# MakerTherapyBadge.net
KiCad netlist of a schematic drawn in EAGLE
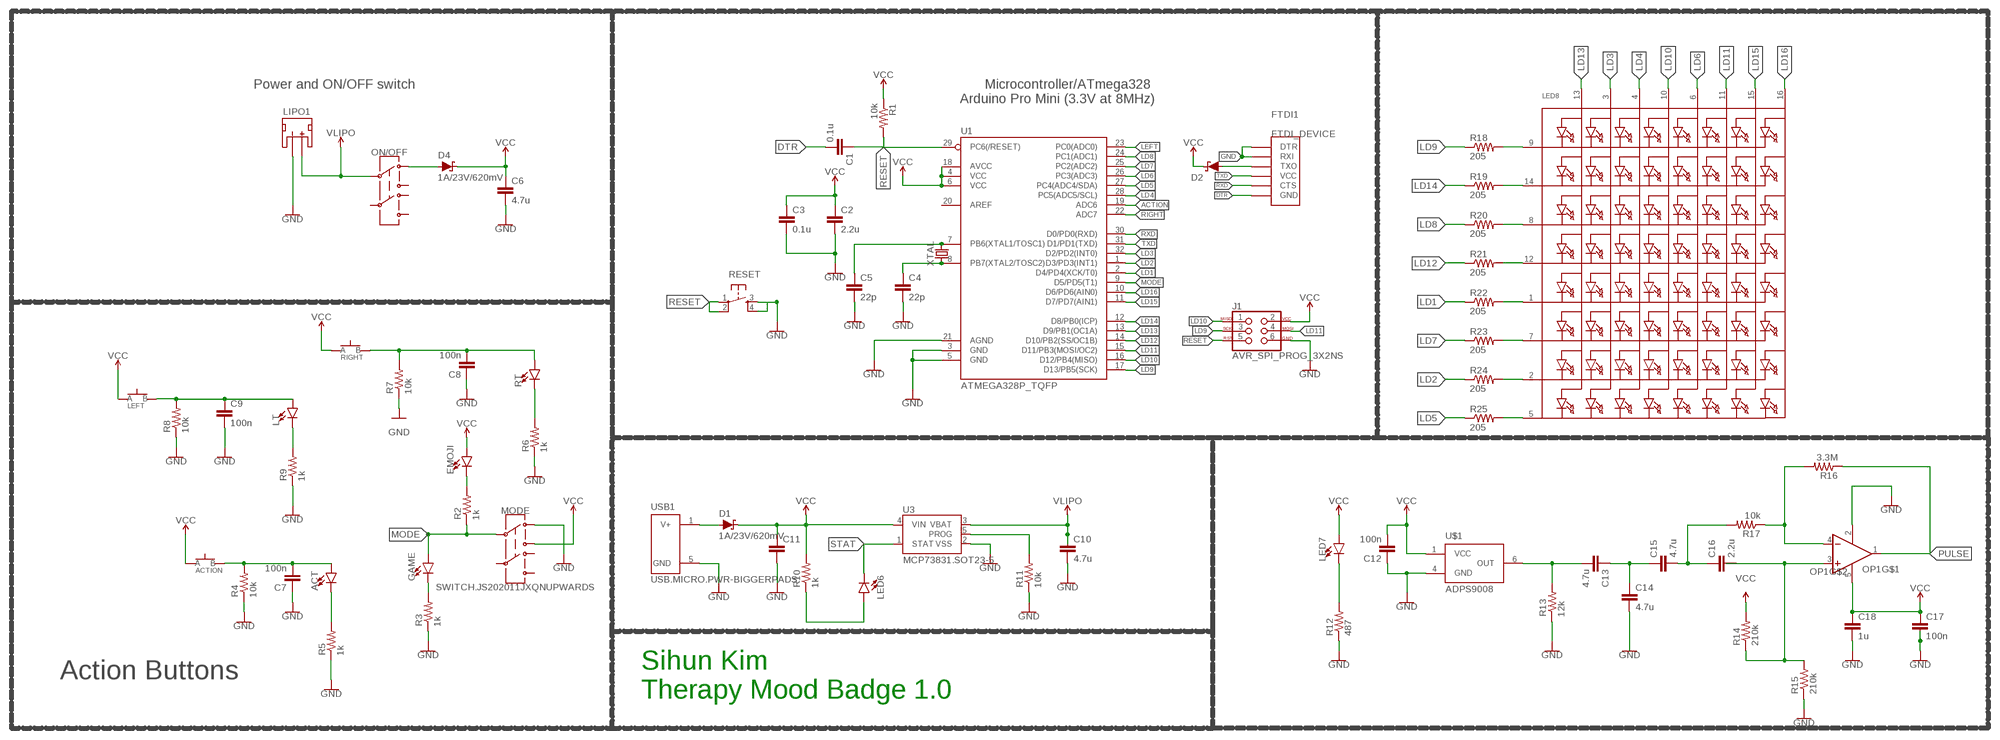
[diagram p0: schematic, sheet 1]

(export (version "E")
  (design (tool "Eeschema 10.0.6"))
  (components
    (comp (ref "ACT")
      (value "LED0603")
      (footprint "eagle-import:LED-0603")
      (libsource (lib "eagle-import") (part "LED0603"))
    )
    (comp (ref "ACTION")
      (value "SPST.KT11P4SM34LFS")
      (footprint "eagle-import:SPST.KT11P4SM34LFS")
      (libsource (lib "eagle-import") (part "SPST.KT11P4SM34LFS"))
    )
    (comp (ref "C1")
      (value "0.1u")
      (footprint "eagle-import:C0603")
      (libsource (lib "eagle-import") (part "CAPACITOR0603"))
    )
    (comp (ref "C2")
      (value "2.2u")
      (footprint "eagle-import:C0603")
      (libsource (lib "eagle-import") (part "CAPACITOR0603"))
    )
    (comp (ref "C3")
      (value "0.1u")
      (footprint "eagle-import:C0603")
      (libsource (lib "eagle-import") (part "CAPACITOR0603"))
    )
    (comp (ref "C4")
      (value "22p")
      (footprint "eagle-import:C0603")
      (libsource (lib "eagle-import") (part "CAPACITOR0603"))
    )
    (comp (ref "C5")
      (value "22p")
      (footprint "eagle-import:C0603")
      (libsource (lib "eagle-import") (part "CAPACITOR0603"))
    )
    (comp (ref "C6")
      (value "4.7u")
      (footprint "eagle-import:C0603")
      (libsource (lib "eagle-import") (part "CAPACITOR0603"))
    )
    (comp (ref "C7")
      (value "100n")
      (footprint "eagle-import:C0603")
      (libsource (lib "eagle-import") (part "CAPACITOR0603"))
    )
    (comp (ref "C8")
      (value "100n")
      (footprint "eagle-import:C0603")
      (libsource (lib "eagle-import") (part "CAPACITOR0603"))
    )
    (comp (ref "C9")
      (value "100n")
      (footprint "eagle-import:C0603")
      (libsource (lib "eagle-import") (part "CAPACITOR0603"))
    )
    (comp (ref "C10")
      (value "4.7u")
      (footprint "eagle-import:C0603")
      (libsource (lib "eagle-import") (part "CAPACITOR0603"))
    )
    (comp (ref "C11")
      (value "CAPACITOR0603")
      (footprint "eagle-import:C0603")
      (libsource (lib "eagle-import") (part "CAPACITOR0603"))
    )
    (comp (ref "C12")
      (value "100n")
      (footprint "eagle-import:C0603")
      (libsource (lib "eagle-import") (part "CAPACITOR0603"))
    )
    (comp (ref "C13")
      (value "4.7u")
      (footprint "eagle-import:C0603")
      (libsource (lib "eagle-import") (part "CAPACITOR0603"))
    )
    (comp (ref "C14")
      (value "4.7u")
      (footprint "eagle-import:C0603")
      (libsource (lib "eagle-import") (part "CAPACITOR0603"))
    )
    (comp (ref "C15")
      (value "4.7u")
      (footprint "eagle-import:C0603")
      (libsource (lib "eagle-import") (part "CAPACITOR0603"))
    )
    (comp (ref "C16")
      (value "2.2u")
      (footprint "eagle-import:C0603")
      (libsource (lib "eagle-import") (part "CAPACITOR0603"))
    )
    (comp (ref "C17")
      (value "100n")
      (footprint "eagle-import:C0603")
      (libsource (lib "eagle-import") (part "CAPACITOR0603"))
    )
    (comp (ref "C18")
      (value "1u")
      (footprint "eagle-import:C0603")
      (libsource (lib "eagle-import") (part "CAPACITOR0603"))
    )
    (comp (ref "D1")
      (value "1A/23V/620mV")
      (footprint "eagle-import:USC")
      (libsource (lib "eagle-import") (part "SCHOTTKY-USC"))
    )
    (comp (ref "D2")
      (value "SCHOTTKY-USC")
      (footprint "eagle-import:USC")
      (libsource (lib "eagle-import") (part "SCHOTTKY-USC"))
    )
    (comp (ref "D4")
      (value "1A/23V/620mV")
      (footprint "eagle-import:USC")
      (libsource (lib "eagle-import") (part "SCHOTTKY-USC"))
    )
    (comp (ref "EMOJI")
      (value "LED0603")
      (footprint "eagle-import:LED-0603")
      (libsource (lib "eagle-import") (part "LED0603"))
    )
    (comp (ref "FTDI1")
      (value "FTDI_DEVICE")
      (footprint "eagle-import:FTDI_DEVICE")
      (libsource (lib "eagle-import") (part "FTDI_DEVICE"))
    )
    (comp (ref "GAME")
      (value "LED0603")
      (footprint "eagle-import:LED-0603")
      (libsource (lib "eagle-import") (part "LED0603"))
    )
    (comp (ref "J1")
      (value "AVR_SPI_PROG_3X2NS")
      (footprint "eagle-import:2X3-NS")
      (libsource (lib "eagle-import") (part "AVR_SPI_PROG_3X2NS"))
    )
    (comp (ref "LED6")
      (value "LED0603")
      (footprint "eagle-import:LED-0603")
      (libsource (lib "eagle-import") (part "LED0603"))
    )
    (comp (ref "LED7")
      (value "LED0603")
      (footprint "eagle-import:LED-0603")
      (libsource (lib "eagle-import") (part "LED0603"))
    )
    (comp (ref "LED8")
      (value "SEGMENT_8X8_ROWCATHODEM12A881UR")
      (footprint "eagle-import:SEGMENT_BL-M12A881UR")
      (libsource (lib "eagle-import") (part "SEGMENT_8X8_ROWCATHODEM12A881UR"))
    )
    (comp (ref "LEFT")
      (value "SPST.KT11P4SM34LFS")
      (footprint "eagle-import:SPST.KT11P4SM34LFS")
      (libsource (lib "eagle-import") (part "SPST.KT11P4SM34LFS"))
    )
    (comp (ref "LIPO1")
      (value "JST_2MM_MALE")
      (footprint "eagle-import:JST-2-SMD")
      (libsource (lib "eagle-import") (part "JST_2MM_MALE"))
    )
    (comp (ref "LT")
      (value "LED0603")
      (footprint "eagle-import:LED-0603")
      (libsource (lib "eagle-import") (part "LED0603"))
    )
    (comp (ref "MODE")
      (value "SWITCH.JS202011JXQNUPWARDS")
      (footprint "eagle-import:SWITCH.00")
      (libsource (lib "eagle-import") (part "SWITCH.JS202011JXQNUPWARDS"))
    )
    (comp (ref "ON/OFF")
      (value "SWITCH.JS202011JXQNUPWARDS")
      (footprint "eagle-import:SWITCH.00")
      (libsource (lib "eagle-import") (part "SWITCH.JS202011JXQNUPWARDS"))
    )
    (comp (ref "OP1")
      (value "OP-SINGLEOT")
      (footprint "eagle-import:SOT23-5")
      (libsource (lib "eagle-import") (part "OP-SINGLEOT"))
    )
    (comp (ref "R1")
      (value "10k")
      (footprint "eagle-import:R0603")
      (libsource (lib "eagle-import") (part "RESISTOR0603"))
    )
    (comp (ref "R2")
      (value "1k")
      (footprint "eagle-import:R0603")
      (libsource (lib "eagle-import") (part "RESISTOR0603"))
    )
    (comp (ref "R3")
      (value "1k")
      (footprint "eagle-import:R0603")
      (libsource (lib "eagle-import") (part "RESISTOR0603"))
    )
    (comp (ref "R4")
      (value "10k")
      (footprint "eagle-import:R0603")
      (libsource (lib "eagle-import") (part "RESISTOR0603"))
    )
    (comp (ref "R5")
      (value "1k")
      (footprint "eagle-import:R0603")
      (libsource (lib "eagle-import") (part "RESISTOR0603"))
    )
    (comp (ref "R6")
      (value "1k")
      (footprint "eagle-import:R0603")
      (libsource (lib "eagle-import") (part "RESISTOR0603"))
    )
    (comp (ref "R7")
      (value "10k")
      (footprint "eagle-import:R0603")
      (libsource (lib "eagle-import") (part "RESISTOR0603"))
    )
    (comp (ref "R8")
      (value "10k")
      (footprint "eagle-import:R0603")
      (libsource (lib "eagle-import") (part "RESISTOR0603"))
    )
    (comp (ref "R9")
      (value "1k")
      (footprint "eagle-import:R0603")
      (libsource (lib "eagle-import") (part "RESISTOR0603"))
    )
    (comp (ref "R10")
      (value "1k")
      (footprint "eagle-import:R0603")
      (libsource (lib "eagle-import") (part "RESISTOR0603"))
    )
    (comp (ref "R11")
      (value "10k")
      (footprint "eagle-import:R0603")
      (libsource (lib "eagle-import") (part "RESISTOR0603"))
    )
    (comp (ref "R12")
      (value "487")
      (footprint "eagle-import:R0603")
      (libsource (lib "eagle-import") (part "RESISTOR0603"))
    )
    (comp (ref "R13")
      (value "12k")
      (footprint "eagle-import:R0603")
      (libsource (lib "eagle-import") (part "RESISTOR0603"))
    )
    (comp (ref "R14")
      (value "210k")
      (footprint "eagle-import:R0603")
      (libsource (lib "eagle-import") (part "RESISTOR0603"))
    )
    (comp (ref "R15")
      (value "210k")
      (footprint "eagle-import:R0603")
      (libsource (lib "eagle-import") (part "RESISTOR0603"))
    )
    (comp (ref "R16")
      (value "3.3M")
      (footprint "eagle-import:R0603")
      (libsource (lib "eagle-import") (part "RESISTOR0603"))
    )
    (comp (ref "R17")
      (value "10k")
      (footprint "eagle-import:R0603")
      (libsource (lib "eagle-import") (part "RESISTOR0603"))
    )
    (comp (ref "R18")
      (value "205")
      (footprint "eagle-import:R0603")
      (libsource (lib "eagle-import") (part "RESISTOR0603"))
    )
    (comp (ref "R19")
      (value "205")
      (footprint "eagle-import:R0603")
      (libsource (lib "eagle-import") (part "RESISTOR0603"))
    )
    (comp (ref "R20")
      (value "205")
      (footprint "eagle-import:R0603")
      (libsource (lib "eagle-import") (part "RESISTOR0603"))
    )
    (comp (ref "R21")
      (value "205")
      (footprint "eagle-import:R0603")
      (libsource (lib "eagle-import") (part "RESISTOR0603"))
    )
    (comp (ref "R22")
      (value "205")
      (footprint "eagle-import:R0603")
      (libsource (lib "eagle-import") (part "RESISTOR0603"))
    )
    (comp (ref "R23")
      (value "205")
      (footprint "eagle-import:R0603")
      (libsource (lib "eagle-import") (part "RESISTOR0603"))
    )
    (comp (ref "R24")
      (value "205")
      (footprint "eagle-import:R0603")
      (libsource (lib "eagle-import") (part "RESISTOR0603"))
    )
    (comp (ref "R25")
      (value "205")
      (footprint "eagle-import:R0603")
      (libsource (lib "eagle-import") (part "RESISTOR0603"))
    )
    (comp (ref "RESET")
      (value "SPST-PTS830GG140")
      (footprint "eagle-import:BUTTON-GULLWING")
      (libsource (lib "eagle-import") (part "SPST-PTS830GG140"))
    )
    (comp (ref "RIGHT")
      (value "SPST.KT11P4SM34LFS")
      (footprint "eagle-import:SPST.KT11P4SM34LFS")
      (libsource (lib "eagle-import") (part "SPST.KT11P4SM34LFS"))
    )
    (comp (ref "RT")
      (value "LED0603")
      (footprint "eagle-import:LED-0603")
      (libsource (lib "eagle-import") (part "LED0603"))
    )
    (comp (ref "U$1")
      (value "ADPS9008")
      (footprint "eagle-import:6-PIN.CHIPLED")
      (libsource (lib "eagle-import") (part "ADPS9008"))
    )
    (comp (ref "U1")
      (value "ATMEGA328P_TQFP")
      (footprint "eagle-import:TQFP32-08")
      (libsource (lib "eagle-import") (part "ATMEGA328P_TQFP"))
    )
    (comp (ref "U3")
      (value "MCP73831.SOT23-5")
      (footprint "eagle-import:SOT23-5")
      (libsource (lib "eagle-import") (part "MCP73831.SOT23-5"))
    )
    (comp (ref "USB1")
      (value "USB.MICRO.PWR-BIGGERPADS")
      (footprint "eagle-import:USB-MICRO-01.BIGGERPADS.PWR")
      (libsource (lib "eagle-import") (part "USB.MICRO.PWR-BIGGERPADS"))
    )
    (comp (ref "XTAL")
      (value "CRYSTAL-CA-310")
      (footprint "eagle-import:CA-301")
      (libsource (lib "eagle-import") (part "CRYSTAL-CA-310"))
    )
  )
  (nets
    (net (code "1") (name "ACTION") (class "Default")
      (node (ref "U1") (pin "19") (pinfunction "ADC6_19") (pintype "bidirectional"))
    )
    (net (code "2") (name "DTR") (class "Default")
      (node (ref "C1") (pin "2") (pinfunction "2_2") (pintype "passive"))
      (node (ref "FTDI1") (pin "GND") (pinfunction "GND_GND") (pintype "bidirectional"))
    )
    (net (code "3") (name "GND") (class "Default")
      (node (ref "C10") (pin "2") (pinfunction "2_2") (pintype "passive"))
      (node (ref "C11") (pin "2") (pinfunction "2_2") (pintype "passive"))
      (node (ref "C12") (pin "1") (pinfunction "1_1") (pintype "passive"))
      (node (ref "C14") (pin "2") (pinfunction "2_2") (pintype "passive"))
      (node (ref "C17") (pin "2") (pinfunction "2_2") (pintype "passive"))
      (node (ref "C18") (pin "2") (pinfunction "2_2") (pintype "passive"))
      (node (ref "C2") (pin "2") (pinfunction "2_2") (pintype "passive"))
      (node (ref "C3") (pin "2") (pinfunction "2_2") (pintype "passive"))
      (node (ref "C4") (pin "2") (pinfunction "2_2") (pintype "passive"))
      (node (ref "C5") (pin "2") (pinfunction "2_2") (pintype "passive"))
      (node (ref "C6") (pin "2") (pinfunction "2_2") (pintype "passive"))
      (node (ref "C7") (pin "1") (pinfunction "1_1") (pintype "passive"))
      (node (ref "C8") (pin "1") (pinfunction "1_1") (pintype "passive"))
      (node (ref "C9") (pin "2") (pinfunction "2_2") (pintype "passive"))
      (node (ref "FTDI1") (pin "DTR") (pinfunction "DTR_DTR") (pintype "bidirectional"))
      (node (ref "FTDI1") (pin "TXO") (pinfunction "RXI_TXO") (pintype "bidirectional"))
      (node (ref "J1") (pin "6") (pinfunction "6_6") (pintype "passive"))
      (node (ref "LIPO1") (pin "1") (pinfunction "-_1") (pintype "bidirectional"))
      (node (ref "MODE") (pin "1") (pinfunction "1_1") (pintype "bidirectional"))
      (node (ref "OP1") (pin "2") (pinfunction "V-_2") (pintype "power_in"))
      (node (ref "R11") (pin "1") (pinfunction "1_1") (pintype "passive"))
      (node (ref "R12") (pin "1") (pinfunction "1_1") (pintype "passive"))
      (node (ref "R13") (pin "1") (pinfunction "1_1") (pintype "passive"))
      (node (ref "R15") (pin "1") (pinfunction "1_1") (pintype "passive"))
      (node (ref "R3") (pin "1") (pinfunction "1_1") (pintype "passive"))
      (node (ref "R4") (pin "1") (pinfunction "1_1") (pintype "passive"))
      (node (ref "R5") (pin "1") (pinfunction "1_1") (pintype "passive"))
      (node (ref "R6") (pin "1") (pinfunction "1_1") (pintype "passive"))
      (node (ref "R7") (pin "1") (pinfunction "1_1") (pintype "passive"))
      (node (ref "R8") (pin "1") (pinfunction "1_1") (pintype "passive"))
      (node (ref "R9") (pin "1") (pinfunction "1_1") (pintype "passive"))
      (node (ref "RESET") (pin "3") (pinfunction "3_3") (pintype "passive"))
      (node (ref "RESET") (pin "4") (pinfunction "4_4") (pintype "passive"))
      (node (ref "U$1") (pin "4") (pinfunction "GND_4") (pintype "bidirectional"))
      (node (ref "U1") (pin "21") (pinfunction "AGND_21") (pintype "bidirectional"))
      (node (ref "U1") (pin "3") (pinfunction "GND_3") (pintype "bidirectional"))
      (node (ref "U1") (pin "5") (pinfunction "GND_5") (pintype "bidirectional"))
      (node (ref "U3") (pin "2") (pinfunction "VSS_2") (pintype "power_in"))
      (node (ref "USB1") (pin "5") (pinfunction "GND_5") (pintype "bidirectional"))
    )
    (net (code "4") (name "LD1") (class "Default")
      (node (ref "R22") (pin "1") (pinfunction "1_1") (pintype "passive"))
      (node (ref "U1") (pin "2") (pinfunction "D4/PD4(XCK/T0)_2") (pintype "bidirectional"))
    )
    (net (code "5") (name "LD2") (class "Default")
      (node (ref "R24") (pin "1") (pinfunction "1_1") (pintype "passive"))
      (node (ref "U1") (pin "1") (pinfunction "D3/PD3(INT1)_1") (pintype "bidirectional"))
    )
    (net (code "6") (name "LD3") (class "Default")
      (node (ref "LED8") (pin "3") (pinfunction "A2_3") (pintype "bidirectional"))
      (node (ref "U1") (pin "32") (pinfunction "D2/PD2(INT0)_32") (pintype "bidirectional"))
    )
    (net (code "7") (name "LD4") (class "Default")
      (node (ref "LED8") (pin "4") (pinfunction "A3_4") (pintype "bidirectional"))
      (node (ref "U1") (pin "28") (pinfunction "PC5(ADC5/SCL)_28") (pintype "bidirectional"))
    )
    (net (code "8") (name "LD5") (class "Default")
      (node (ref "R25") (pin "1") (pinfunction "1_1") (pintype "passive"))
      (node (ref "U1") (pin "27") (pinfunction "PC4(ADC4/SDA)_27") (pintype "bidirectional"))
    )
    (net (code "9") (name "LD6") (class "Default")
      (node (ref "LED8") (pin "6") (pinfunction "A5_6") (pintype "bidirectional"))
      (node (ref "U1") (pin "26") (pinfunction "PC3(ADC3)_26") (pintype "bidirectional"))
    )
    (net (code "10") (name "LD7") (class "Default")
      (node (ref "R23") (pin "1") (pinfunction "1_1") (pintype "passive"))
      (node (ref "U1") (pin "25") (pinfunction "PC2(ADC2)_25") (pintype "bidirectional"))
    )
    (net (code "11") (name "LD8") (class "Default")
      (node (ref "R20") (pin "1") (pinfunction "1_1") (pintype "passive"))
      (node (ref "U1") (pin "24") (pinfunction "PC1(ADC1)_24") (pintype "bidirectional"))
    )
    (net (code "12") (name "LD9") (class "Default")
      (node (ref "J1") (pin "3") (pinfunction "3_3") (pintype "passive"))
      (node (ref "R18") (pin "1") (pinfunction "1_1") (pintype "passive"))
      (node (ref "U1") (pin "17") (pinfunction "D13/PB5(SCK)_17") (pintype "bidirectional"))
    )
    (net (code "13") (name "LD10") (class "Default")
      (node (ref "J1") (pin "1") (pinfunction "1_1") (pintype "passive"))
      (node (ref "LED8") (pin "10") (pinfunction "A4_10") (pintype "bidirectional"))
      (node (ref "U1") (pin "16") (pinfunction "D12/PB4(MISO)_16") (pintype "bidirectional"))
    )
    (net (code "14") (name "LD11") (class "Default")
      (node (ref "J1") (pin "4") (pinfunction "4_4") (pintype "passive"))
      (node (ref "LED8") (pin "11") (pinfunction "A6_11") (pintype "bidirectional"))
      (node (ref "U1") (pin "15") (pinfunction "D11/PB3(MOSI/OC2)_15") (pintype "bidirectional"))
    )
    (net (code "15") (name "LD12") (class "Default")
      (node (ref "R21") (pin "1") (pinfunction "1_1") (pintype "passive"))
      (node (ref "U1") (pin "14") (pinfunction "D10/PB2(SS/OC1B)_14") (pintype "bidirectional"))
    )
    (net (code "16") (name "LD13") (class "Default")
      (node (ref "LED8") (pin "13") (pinfunction "A1_13") (pintype "bidirectional"))
      (node (ref "U1") (pin "13") (pinfunction "D9/PB1(OC1A)_13") (pintype "bidirectional"))
    )
    (net (code "17") (name "LD14") (class "Default")
      (node (ref "R19") (pin "1") (pinfunction "1_1") (pintype "passive"))
      (node (ref "U1") (pin "12") (pinfunction "D8/PB0(ICP)_12") (pintype "bidirectional"))
    )
    (net (code "18") (name "LD15") (class "Default")
      (node (ref "LED8") (pin "15") (pinfunction "A7_15") (pintype "bidirectional"))
      (node (ref "U1") (pin "11") (pinfunction "D7/PD7(AIN1)_11") (pintype "bidirectional"))
    )
    (net (code "19") (name "LD16") (class "Default")
      (node (ref "LED8") (pin "16") (pinfunction "A8_16") (pintype "bidirectional"))
      (node (ref "U1") (pin "10") (pinfunction "D6/PD6(AIN0)_10") (pintype "bidirectional"))
    )
    (net (code "20") (name "LEFT") (class "Default")
      (node (ref "U1") (pin "23") (pinfunction "PC0(ADC0)_23") (pintype "bidirectional"))
    )
    (net (code "21") (name "MODE") (class "Default")
      (node (ref "GAME") (pin "A") (pinfunction "A_A") (pintype "passive"))
      (node (ref "MODE") (pin "2") (pinfunction "2_2") (pintype "bidirectional"))
      (node (ref "R2") (pin "1") (pinfunction "1_1") (pintype "passive"))
      (node (ref "U1") (pin "9") (pinfunction "D5/PD5(T1)_9") (pintype "bidirectional"))
    )
    (net (code "22") (name "Net-(ACT-PadA)") (class "Default")
      (node (ref "ACT") (pin "A") (pinfunction "A_A") (pintype "passive"))
      (node (ref "ACTION") (pin "3") (pinfunction "B_3") (pintype "bidirectional"))
      (node (ref "ACTION") (pin "4") (pinfunction "B_4") (pintype "bidirectional"))
      (node (ref "C7") (pin "2") (pinfunction "2_2") (pintype "passive"))
      (node (ref "R4") (pin "2") (pinfunction "2_2") (pintype "passive"))
    )
    (net (code "23") (name "Net-(ACT-PadC)") (class "Default")
      (node (ref "ACT") (pin "C") (pinfunction "C_C") (pintype "passive"))
      (node (ref "R5") (pin "2") (pinfunction "2_2") (pintype "passive"))
    )
    (net (code "24") (name "Net-(C8-Pad2)") (class "Default")
      (node (ref "C8") (pin "2") (pinfunction "2_2") (pintype "passive"))
      (node (ref "R7") (pin "2") (pinfunction "2_2") (pintype "passive"))
      (node (ref "RIGHT") (pin "3") (pinfunction "B_3") (pintype "bidirectional"))
      (node (ref "RIGHT") (pin "4") (pinfunction "B_4") (pintype "bidirectional"))
      (node (ref "RT") (pin "A") (pinfunction "A_A") (pintype "passive"))
    )
    (net (code "25") (name "Net-(C9-Pad1)") (class "Default")
      (node (ref "C9") (pin "1") (pinfunction "1_1") (pintype "passive"))
      (node (ref "LEFT") (pin "3") (pinfunction "B_3") (pintype "bidirectional"))
      (node (ref "LEFT") (pin "4") (pinfunction "B_4") (pintype "bidirectional"))
      (node (ref "LT") (pin "A") (pinfunction "A_A") (pintype "passive"))
      (node (ref "R8") (pin "2") (pinfunction "2_2") (pintype "passive"))
    )
    (net (code "26") (name "Net-(C13-Pad1)") (class "Default")
      (node (ref "C13") (pin "1") (pinfunction "1_1") (pintype "passive"))
      (node (ref "C14") (pin "1") (pinfunction "1_1") (pintype "passive"))
      (node (ref "C15") (pin "1") (pinfunction "1_1") (pintype "passive"))
    )
    (net (code "27") (name "Net-(C15-Pad2)") (class "Default")
      (node (ref "C15") (pin "2") (pinfunction "2_2") (pintype "passive"))
      (node (ref "C16") (pin "1") (pinfunction "1_1") (pintype "passive"))
      (node (ref "R17") (pin "2") (pinfunction "2_2") (pintype "passive"))
    )
    (net (code "28") (name "Net-(D1-A)") (class "Default")
      (node (ref "D1") (pin "+") (pinfunction "A_+") (pintype "passive"))
      (node (ref "USB1") (pin "1") (pinfunction "V+_1") (pintype "bidirectional"))
    )
    (net (code "29") (name "Net-(D2-A)") (class "Default")
      (node (ref "D2") (pin "+") (pinfunction "A_+") (pintype "passive"))
      (node (ref "FTDI1") (pin "RXI") (pinfunction "TXO_RXI") (pintype "bidirectional"))
    )
    (net (code "30") (name "Net-(D4-A)") (class "Default")
      (node (ref "D4") (pin "+") (pinfunction "A_+") (pintype "passive"))
      (node (ref "ON/OFF") (pin "1") (pinfunction "1_1") (pintype "bidirectional"))
    )
    (net (code "31") (name "Net-(EMOJI-PadC)") (class "Default")
      (node (ref "EMOJI") (pin "C") (pinfunction "C_C") (pintype "passive"))
      (node (ref "R2") (pin "2") (pinfunction "2_2") (pintype "passive"))
    )
    (net (code "32") (name "Net-(GAME-PadC)") (class "Default")
      (node (ref "GAME") (pin "C") (pinfunction "C_C") (pintype "passive"))
      (node (ref "R3") (pin "2") (pinfunction "2_2") (pintype "passive"))
    )
    (net (code "33") (name "Net-(LED6-PadA)") (class "Default")
      (node (ref "LED6") (pin "A") (pinfunction "A_A") (pintype "passive"))
      (node (ref "R10") (pin "1") (pinfunction "1_1") (pintype "passive"))
    )
    (net (code "34") (name "Net-(LED7-PadC)") (class "Default")
      (node (ref "LED7") (pin "C") (pinfunction "C_C") (pintype "passive"))
      (node (ref "R12") (pin "2") (pinfunction "2_2") (pintype "passive"))
    )
    (net (code "35") (name "Net-(LED8-K1)") (class "Default")
      (node (ref "LED8") (pin "9") (pinfunction "K1_9") (pintype "bidirectional"))
      (node (ref "R18") (pin "2") (pinfunction "2_2") (pintype "passive"))
    )
    (net (code "36") (name "Net-(LED8-K2)") (class "Default")
      (node (ref "LED8") (pin "14") (pinfunction "K2_14") (pintype "bidirectional"))
      (node (ref "R19") (pin "2") (pinfunction "2_2") (pintype "passive"))
    )
    (net (code "37") (name "Net-(LED8-K3)") (class "Default")
      (node (ref "LED8") (pin "8") (pinfunction "K3_8") (pintype "bidirectional"))
      (node (ref "R20") (pin "2") (pinfunction "2_2") (pintype "passive"))
    )
    (net (code "38") (name "Net-(LED8-K4)") (class "Default")
      (node (ref "LED8") (pin "12") (pinfunction "K4_12") (pintype "bidirectional"))
      (node (ref "R21") (pin "2") (pinfunction "2_2") (pintype "passive"))
    )
    (net (code "39") (name "Net-(LED8-K5)") (class "Default")
      (node (ref "LED8") (pin "1") (pinfunction "K5_1") (pintype "bidirectional"))
      (node (ref "R22") (pin "2") (pinfunction "2_2") (pintype "passive"))
    )
    (net (code "40") (name "Net-(LED8-K6)") (class "Default")
      (node (ref "LED8") (pin "7") (pinfunction "K6_7") (pintype "bidirectional"))
      (node (ref "R23") (pin "2") (pinfunction "2_2") (pintype "passive"))
    )
    (net (code "41") (name "Net-(LED8-K7)") (class "Default")
      (node (ref "LED8") (pin "2") (pinfunction "K7_2") (pintype "bidirectional"))
      (node (ref "R24") (pin "2") (pinfunction "2_2") (pintype "passive"))
    )
    (net (code "42") (name "Net-(LED8-K8)") (class "Default")
      (node (ref "LED8") (pin "5") (pinfunction "K8_5") (pintype "bidirectional"))
      (node (ref "R25") (pin "2") (pinfunction "2_2") (pintype "passive"))
    )
    (net (code "43") (name "Net-(LT-PadC)") (class "Default")
      (node (ref "LT") (pin "C") (pinfunction "C_C") (pintype "passive"))
      (node (ref "R9") (pin "2") (pinfunction "2_2") (pintype "passive"))
    )
    (net (code "44") (name "Net-(OP1A-+IN)") (class "Default")
      (node (ref "C16") (pin "2") (pinfunction "2_2") (pintype "passive"))
      (node (ref "OP1") (pin "3") (pinfunction "+IN_3") (pintype "input"))
      (node (ref "R14") (pin "1") (pinfunction "1_1") (pintype "passive"))
      (node (ref "R15") (pin "2") (pinfunction "2_2") (pintype "passive"))
    )
    (net (code "45") (name "Net-(OP1A--IN)") (class "Default")
      (node (ref "OP1") (pin "4") (pinfunction "-IN_4") (pintype "input"))
      (node (ref "R16") (pin "2") (pinfunction "2_2") (pintype "passive"))
      (node (ref "R17") (pin "1") (pinfunction "1_1") (pintype "passive"))
    )
    (net (code "46") (name "Net-(R6-Pad2)") (class "Default")
      (node (ref "R6") (pin "2") (pinfunction "2_2") (pintype "passive"))
      (node (ref "RT") (pin "C") (pinfunction "C_C") (pintype "passive"))
    )
    (net (code "47") (name "Net-(U$1-OUT)") (class "Default")
      (node (ref "C13") (pin "2") (pinfunction "2_2") (pintype "passive"))
      (node (ref "R13") (pin "2") (pinfunction "2_2") (pintype "passive"))
      (node (ref "U$1") (pin "6") (pinfunction "OUT_6") (pintype "bidirectional"))
    )
    (net (code "48") (name "Net-(U1-PB6(XTAL1{slash}TOSC1))") (class "Default")
      (node (ref "C5") (pin "1") (pinfunction "1_1") (pintype "passive"))
      (node (ref "U1") (pin "7") (pinfunction "PB6(XTAL1/TOSC1)_7") (pintype "bidirectional"))
      (node (ref "XTAL") (pin "2") (pinfunction "2_2") (pintype "passive"))
    )
    (net (code "49") (name "Net-(U1-PB7(XTAL2{slash}TOSC2))") (class "Default")
      (node (ref "C4") (pin "1") (pinfunction "1_1") (pintype "passive"))
      (node (ref "U1") (pin "8") (pinfunction "PB7(XTAL2/TOSC2)_8") (pintype "bidirectional"))
      (node (ref "XTAL") (pin "1") (pinfunction "1_1") (pintype "passive"))
    )
    (net (code "50") (name "Net-(U3-PROG)") (class "Default")
      (node (ref "R11") (pin "2") (pinfunction "2_2") (pintype "passive"))
      (node (ref "U3") (pin "5") (pinfunction "PROG_5") (pintype "input"))
    )
    (net (code "51") (name "PULSE") (class "Default")
      (node (ref "OP1") (pin "1") (pinfunction "OUT_1") (pintype "output"))
      (node (ref "R16") (pin "1") (pinfunction "1_1") (pintype "passive"))
    )
    (net (code "52") (name "RESET") (class "Default")
      (node (ref "C1") (pin "1") (pinfunction "1_1") (pintype "passive"))
      (node (ref "J1") (pin "5") (pinfunction "5_5") (pintype "passive"))
      (node (ref "R1") (pin "2") (pinfunction "2_2") (pintype "passive"))
      (node (ref "RESET") (pin "1") (pinfunction "1_1") (pintype "passive"))
      (node (ref "RESET") (pin "2") (pinfunction "2_2") (pintype "passive"))
      (node (ref "U1") (pin "29") (pinfunction "PC6(/RESET)_29") (pintype "bidirectional"))
    )
    (net (code "53") (name "RIGHT") (class "Default")
      (node (ref "U1") (pin "22") (pinfunction "ADC7_22") (pintype "bidirectional"))
    )
    (net (code "54") (name "RXD") (class "Default")
      (node (ref "FTDI1") (pin "CTS") (pinfunction "CTS_CTS") (pintype "bidirectional"))
      (node (ref "U1") (pin "30") (pinfunction "D0/PD0(RXD)_30") (pintype "bidirectional"))
    )
    (net (code "55") (name "STAT") (class "Default")
      (node (ref "LED6") (pin "C") (pinfunction "C_C") (pintype "passive"))
      (node (ref "U3") (pin "1") (pinfunction "STAT_1") (pintype "output"))
    )
    (net (code "56") (name "TXD") (class "Default")
      (node (ref "FTDI1") (pin "VCC") (pinfunction "VCC_VCC") (pintype "bidirectional"))
      (node (ref "U1") (pin "31") (pinfunction "D1/PD1(TXD)_31") (pintype "bidirectional"))
    )
    (net (code "57") (name "VCC") (class "Default")
      (node (ref "ACTION") (pin "1") (pinfunction "A_1") (pintype "bidirectional"))
      (node (ref "ACTION") (pin "2") (pinfunction "A_2") (pintype "bidirectional"))
      (node (ref "C11") (pin "1") (pinfunction "1_1") (pintype "passive"))
      (node (ref "C12") (pin "2") (pinfunction "2_2") (pintype "passive"))
      (node (ref "C17") (pin "1") (pinfunction "1_1") (pintype "passive"))
      (node (ref "C18") (pin "1") (pinfunction "1_1") (pintype "passive"))
      (node (ref "C2") (pin "1") (pinfunction "1_1") (pintype "passive"))
      (node (ref "C3") (pin "1") (pinfunction "1_1") (pintype "passive"))
      (node (ref "C6") (pin "1") (pinfunction "1_1") (pintype "passive"))
      (node (ref "D1") (pin "-") (pinfunction "C_-") (pintype "passive"))
      (node (ref "D2") (pin "-") (pinfunction "C_-") (pintype "passive"))
      (node (ref "D4") (pin "-") (pinfunction "C_-") (pintype "passive"))
      (node (ref "EMOJI") (pin "A") (pinfunction "A_A") (pintype "passive"))
      (node (ref "J1") (pin "2") (pinfunction "2_2") (pintype "passive"))
      (node (ref "LED7") (pin "A") (pinfunction "A_A") (pintype "passive"))
      (node (ref "LEFT") (pin "1") (pinfunction "A_1") (pintype "bidirectional"))
      (node (ref "LEFT") (pin "2") (pinfunction "A_2") (pintype "bidirectional"))
      (node (ref "MODE") (pin "3") (pinfunction "3_3") (pintype "bidirectional"))
      (node (ref "OP1") (pin "5") (pinfunction "V+_5") (pintype "power_in"))
      (node (ref "R1") (pin "1") (pinfunction "1_1") (pintype "passive"))
      (node (ref "R10") (pin "2") (pinfunction "2_2") (pintype "passive"))
      (node (ref "R14") (pin "2") (pinfunction "2_2") (pintype "passive"))
      (node (ref "RIGHT") (pin "1") (pinfunction "A_1") (pintype "bidirectional"))
      (node (ref "RIGHT") (pin "2") (pinfunction "A_2") (pintype "bidirectional"))
      (node (ref "U$1") (pin "1") (pinfunction "VCC_1") (pintype "bidirectional"))
      (node (ref "U1") (pin "18") (pinfunction "AVCC_18") (pintype "bidirectional"))
      (node (ref "U1") (pin "4") (pinfunction "VCC_4") (pintype "bidirectional"))
      (node (ref "U1") (pin "6") (pinfunction "VCC_6") (pintype "bidirectional"))
      (node (ref "U3") (pin "4") (pinfunction "VIN_4") (pintype "power_in"))
    )
    (net (code "58") (name "VLIPO") (class "Default")
      (node (ref "C10") (pin "1") (pinfunction "1_1") (pintype "passive"))
      (node (ref "LIPO1") (pin "2") (pinfunction "+_2") (pintype "bidirectional"))
      (node (ref "ON/OFF") (pin "2") (pinfunction "2_2") (pintype "bidirectional"))
      (node (ref "U3") (pin "3") (pinfunction "VBAT_3") (pintype "power_in"))
    )
    (net (code "59") (name "unconnected-(LIPO1-PAD1-PadNC1)") (class "Default")
      (node (ref "LIPO1") (pin "NC1") (pinfunction "PAD1_NC1") (pintype "bidirectional"))
    )
    (net (code "60") (name "unconnected-(LIPO1-PAD2-PadNC2)") (class "Default")
      (node (ref "LIPO1") (pin "NC2") (pinfunction "PAD2_NC2") (pintype "bidirectional"))
    )
    (net (code "61") (name "unconnected-(MODE-4-Pad5)") (class "Default")
      (node (ref "MODE") (pin "5") (pinfunction "4_5") (pintype "bidirectional"))
    )
    (net (code "62") (name "unconnected-(MODE-5-Pad6)") (class "Default")
      (node (ref "MODE") (pin "6") (pinfunction "5_6") (pintype "bidirectional"))
    )
    (net (code "63") (name "unconnected-(MODE-6-Pad7)") (class "Default")
      (node (ref "MODE") (pin "7") (pinfunction "6_7") (pintype "bidirectional"))
    )
    (net (code "64") (name "unconnected-(ON/OFF-4-Pad5)") (class "Default")
      (node (ref "ON/OFF") (pin "5") (pinfunction "4_5") (pintype "bidirectional"))
    )
    (net (code "65") (name "unconnected-(ON/OFF-5-Pad6)") (class "Default")
      (node (ref "ON/OFF") (pin "6") (pinfunction "5_6") (pintype "bidirectional"))
    )
    (net (code "66") (name "unconnected-(ON/OFF-6-Pad7)") (class "Default")
      (node (ref "ON/OFF") (pin "7") (pinfunction "6_7") (pintype "bidirectional"))
    )
    (net (code "67") (name "unconnected-(ON/OFF-Pad3)") (class "Default")
      (node (ref "ON/OFF") (pin "3") (pinfunction "3_3") (pintype "bidirectional"))
    )
    (net (code "68") (name "unconnected-(U1-AREF-Pad20)") (class "Default")
      (node (ref "U1") (pin "20") (pinfunction "AREF_20") (pintype "bidirectional"))
    )
  )
)
